# Boost.net
KiCad netlist of a schematic drawn in EAGLE
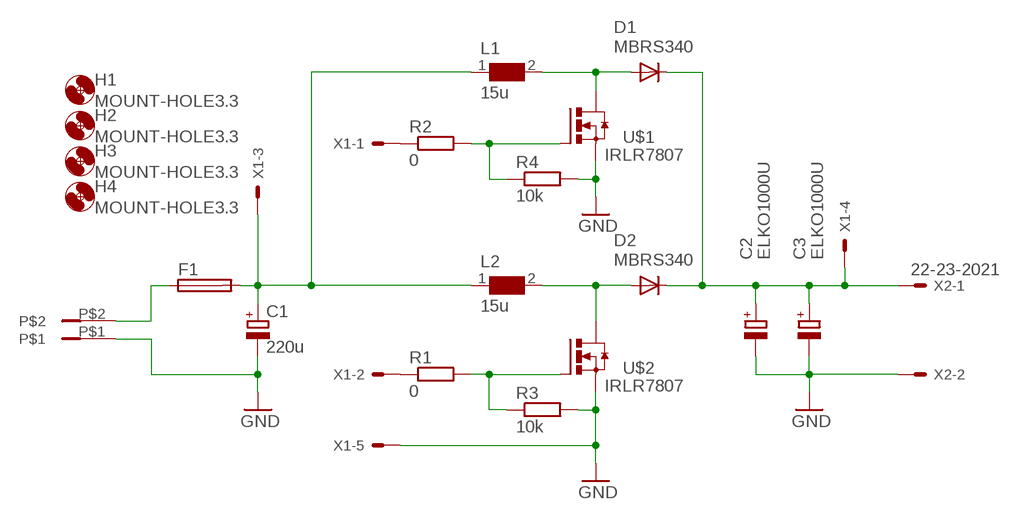
[diagram p0: schematic, sheet 1]

(export (version "E")
  (design (tool "Eeschema 10.0.6"))
  (components
    (comp (ref "C1")
      (value "220u")
      (footprint "eagle-import:PANASONIC_F")
      (libsource (lib "eagle-import") (part "CPOL-EUF"))
    )
    (comp (ref "C2")
      (value "ELKO1000U")
      (footprint "eagle-import:J16")
      (libsource (lib "eagle-import") (part "ELKO1000U"))
    )
    (comp (ref "C3")
      (value "ELKO1000U")
      (footprint "eagle-import:J16")
      (libsource (lib "eagle-import") (part "ELKO1000U"))
    )
    (comp (ref "D1")
      (value "MBRS340")
      (footprint "eagle-import:SMC")
      (libsource (lib "eagle-import") (part "DIODE-SMC"))
    )
    (comp (ref "D2")
      (value "MBRS340")
      (footprint "eagle-import:SMC")
      (libsource (lib "eagle-import") (part "DIODE-SMC"))
    )
    (comp (ref "F1")
      (value "SH22,5")
      (footprint "eagle-import:SH22,5")
      (fields (field (name "MF") "SCHURTER") (field (name "MPN") "0031.8201"))
      (libsource (lib "eagle-import") (part "SH22,5"))
    )
    (comp (ref "H1")
      (value "MOUNT-HOLE3.3")
      (footprint "eagle-import:3,3")
      (libsource (lib "eagle-import") (part "MOUNT-HOLE3.3"))
    )
    (comp (ref "H2")
      (value "MOUNT-HOLE3.3")
      (footprint "eagle-import:3,3")
      (libsource (lib "eagle-import") (part "MOUNT-HOLE3.3"))
    )
    (comp (ref "H3")
      (value "MOUNT-HOLE3.3")
      (footprint "eagle-import:3,3")
      (libsource (lib "eagle-import") (part "MOUNT-HOLE3.3"))
    )
    (comp (ref "H4")
      (value "MOUNT-HOLE3.3")
      (footprint "eagle-import:3,3")
      (libsource (lib "eagle-import") (part "MOUNT-HOLE3.3"))
    )
    (comp (ref "L1")
      (value "15u")
      (footprint "eagle-import:WE-PD_1260_1245_1280_1210")
      (fields (field (name "MPN") "7447709150"))
      (libsource (lib "eagle-import") (part "DROSSEL-WE-PD_1260/1245/1280/1210-7447709150"))
    )
    (comp (ref "L2")
      (value "15u")
      (footprint "eagle-import:WE-PD_1260_1245_1280_1210")
      (fields (field (name "MPN") "7447709150"))
      (libsource (lib "eagle-import") (part "DROSSEL-WE-PD_1260/1245/1280/1210-7447709150"))
    )
    (comp (ref "R1")
      (value "0")
      (footprint "eagle-import:MINI_MELF-0204W")
      (libsource (lib "eagle-import") (part "R-EU_MELF0204W"))
    )
    (comp (ref "R2")
      (value "0")
      (footprint "eagle-import:MINI_MELF-0204W")
      (libsource (lib "eagle-import") (part "R-EU_MELF0204W"))
    )
    (comp (ref "R3")
      (value "10k")
      (footprint "eagle-import:MINI_MELF-0204W")
      (libsource (lib "eagle-import") (part "R-EU_MELF0204W"))
    )
    (comp (ref "R4")
      (value "10k")
      (footprint "eagle-import:MINI_MELF-0204W")
      (libsource (lib "eagle-import") (part "R-EU_MELF0204W"))
    )
    (comp (ref "U$1")
      (value "IRLR7807")
      (footprint "eagle-import:D-PAK")
      (libsource (lib "eagle-import") (part "IRLR7807"))
    )
    (comp (ref "U$2")
      (value "IRLR7807")
      (footprint "eagle-import:D-PAK")
      (libsource (lib "eagle-import") (part "IRLR7807"))
    )
    (comp (ref "U$3")
      (value "RIACON-2")
      (footprint "eagle-import:RIACON2")
      (libsource (lib "eagle-import") (part "RIACON-2"))
    )
    (comp (ref "X1")
      (value "22-23-2051")
      (footprint "eagle-import:22-23-2051")
      (fields (field (name "MF") "MOLEX"))
      (libsource (lib "eagle-import") (part "22-23-2051"))
    )
    (comp (ref "X2")
      (value "22-23-2021")
      (footprint "eagle-import:22-23-2021")
      (fields (field (name "MF") "MOLEX"))
      (libsource (lib "eagle-import") (part "22-23-2021"))
    )
  )
  (nets
    (net (code "1") (name "GND") (class "Default")
      (node (ref "C1") (pin "-") (pinfunction "-_-") (pintype "passive"))
      (node (ref "C2") (pin "-") (pinfunction "-_-") (pintype "passive"))
      (node (ref "C3") (pin "-") (pinfunction "-_-") (pintype "passive"))
      (node (ref "R3") (pin "2") (pinfunction "2_2") (pintype "passive"))
      (node (ref "R4") (pin "2") (pinfunction "2_2") (pintype "passive"))
      (node (ref "U$1") (pin "3") (pinfunction "S_3") (pintype "passive"))
      (node (ref "U$2") (pin "3") (pinfunction "S_3") (pintype "passive"))
      (node (ref "U$3") (pin "P$1") (pinfunction "P$1_P$1") (pintype "bidirectional"))
      (node (ref "X1") (pin "5") (pinfunction "S_5") (pintype "passive"))
      (node (ref "X2") (pin "2") (pinfunction "S_2") (pintype "passive"))
    )
    (net (code "2") (name "Net-(F1-Pad1)") (class "Default")
      (node (ref "F1") (pin "1") (pinfunction "1_1") (pintype "passive"))
      (node (ref "U$3") (pin "P$2") (pinfunction "P$2_P$2") (pintype "bidirectional"))
    )
    (net (code "3") (name "Net-(U$1-D)") (class "Default")
      (node (ref "D1") (pin "A") (pinfunction "A_A") (pintype "passive"))
      (node (ref "L1") (pin "2") (pinfunction "2_2") (pintype "passive"))
      (node (ref "U$1") (pin "4") (pinfunction "D_4") (pintype "passive"))
    )
    (net (code "4") (name "Net-(U$1-G)") (class "Default")
      (node (ref "R2") (pin "2") (pinfunction "2_2") (pintype "passive"))
      (node (ref "R4") (pin "1") (pinfunction "1_1") (pintype "passive"))
      (node (ref "U$1") (pin "1") (pinfunction "G_1") (pintype "passive"))
    )
    (net (code "5") (name "Net-(U$2-D)") (class "Default")
      (node (ref "D2") (pin "A") (pinfunction "A_A") (pintype "passive"))
      (node (ref "L2") (pin "2") (pinfunction "2_2") (pintype "passive"))
      (node (ref "U$2") (pin "4") (pinfunction "D_4") (pintype "passive"))
    )
    (net (code "6") (name "Net-(U$2-G)") (class "Default")
      (node (ref "R1") (pin "2") (pinfunction "2_2") (pintype "passive"))
      (node (ref "R3") (pin "1") (pinfunction "1_1") (pintype "passive"))
      (node (ref "U$2") (pin "1") (pinfunction "G_1") (pintype "passive"))
    )
    (net (code "7") (name "Net-(X1A-S)") (class "Default")
      (node (ref "R2") (pin "1") (pinfunction "1_1") (pintype "passive"))
      (node (ref "X1") (pin "1") (pinfunction "S_1") (pintype "passive"))
    )
    (net (code "8") (name "Net-(X1B-S)") (class "Default")
      (node (ref "R1") (pin "1") (pinfunction "1_1") (pintype "passive"))
      (node (ref "X1") (pin "2") (pinfunction "S_2") (pintype "passive"))
    )
    (net (code "9") (name "Net-(X1C-S)") (class "Default")
      (node (ref "C1") (pin "+") (pinfunction "+_+") (pintype "passive"))
      (node (ref "F1") (pin "2") (pinfunction "2_2") (pintype "passive"))
      (node (ref "L1") (pin "1") (pinfunction "1_1") (pintype "passive"))
      (node (ref "L2") (pin "1") (pinfunction "1_1") (pintype "passive"))
      (node (ref "X1") (pin "3") (pinfunction "S_3") (pintype "passive"))
    )
    (net (code "10") (name "Net-(X1D-S)") (class "Default")
      (node (ref "C2") (pin "+") (pinfunction "+_+") (pintype "passive"))
      (node (ref "C3") (pin "+") (pinfunction "+_+") (pintype "passive"))
      (node (ref "D1") (pin "C") (pinfunction "C_C") (pintype "passive"))
      (node (ref "D2") (pin "C") (pinfunction "C_C") (pintype "passive"))
      (node (ref "X1") (pin "4") (pinfunction "S_4") (pintype "passive"))
      (node (ref "X2") (pin "1") (pinfunction "S_1") (pintype "passive"))
    )
  )
)
